# Relay.net
KiCad netlist of a schematic drawn in Altium Designer
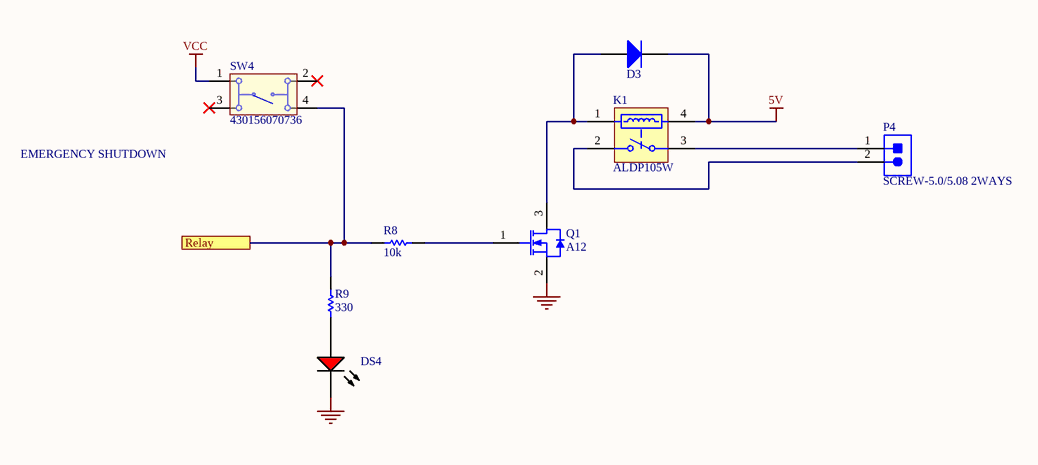
[diagram p0: Relay.SchDoc]

(export (version "E")
  (design (tool "Eeschema 10.0.6"))
  (components
    (comp (ref "D3")
      (value "MMSD4148T3G")
      (footprint "ONSC-SOD123-2-425G-04_V")
      (description "Switching Diode, 100 V, 200 mA, -55 to 150 degC, 2-Pin SOD123 (425), RoHS, Tape and Reel")
      (fields (field (name "MANUFACTURER") "ON Semiconductor"))
      (libsource (lib "Altium Content Vault") (part "ONSC-MMSD4148-SOD123-2"))
    )
    (comp (ref "DS4")
      (value "TLMS1100-GS08")
      (footprint "VISH-TLMX1100_V")
      (description "LED, RED, 2.1 V, -40 to 100 degC, 2-Pin SMD (0603), RoHS, Tape and Reel")
      (fields (field (name "TOLERANCE") "5%"))
      (libsource (lib "Altium Content Vault") (part "LED-RED-AK-2"))
    )
    (comp (ref "K1")
      (value "ALDP105W")
      (footprint "PNSC-LD-P-4-2050x720x1530_V")
      (fields (field (name "MANUFACTURER") "Panasonic"))
      (libsource (lib "Altium Content Vault") (part "PNSC-ALDP105W-LD-P-4-2050x720x1530-4"))
    )
    (comp (ref "P4")
      (value "SCREW-5.0/5.08 2WAYS")
      (footprint "SCREW-5.0-2WAYS_V")
      (description "Socket, Screw Terminal Block, 2 Way, 5.0 mm Pitch, 90 Degree Angle, Through-Hole")
      (fields (field (name "MANUFACTURER") "No Vendor"))
      (libsource (lib "Altium Content Vault") (part "SCREW-2WAYS"))
    )
    (comp (ref "Q1")
      (value "A12")
      (footprint "INTR-SOT-23-3_V")
      (fields (field (name "MANUFACTURER") "International Rectifier"))
      (libsource (lib "Altium Content Vault") (part "NEMOS-GSD-3"))
    )
    (comp (ref "R8")
      (value "10k")
      (footprint "RESC0805(2012)_L")
      (description "10K2 0.125W 1% 0805 (2012 Metric)  SMD")
      (fields (field (name "TOLERANCE") "1 %") (field (name "POWER") "0.125 W"))
      (libsource (lib "Altium Content Vault") (part "RES"))
    )
    (comp (ref "R9")
      (value "330")
      (footprint "RESC0805(2012)_L")
      (description "10K2 0.125W 1% 0805 (2012 Metric)  SMD")
      (fields (field (name "TOLERANCE") "1 %") (field (name "POWER") "0.125 W"))
      (libsource (lib "Altium Content Vault") (part "RES"))
    )
    (comp (ref "SW4")
      (value "430156070736")
      (footprint "430156070736")
      (description "WS-TATV THT Tact Switch 6X6 mm")
      (fields (field (name "MANUFACTURER") "Wuerth Elektronik"))
      (libsource (lib "Altium Content Vault") (part "WE-TACT-SW-4"))
    )
  )
  (nets
    (net (code "1") (name "/Relay") (class "Default")
      (node (ref "R8") (pin "2") (pinfunction "2_2") (pintype "passive"))
      (node (ref "R9") (pin "1") (pinfunction "1_1") (pintype "passive"))
      (node (ref "SW4") (pin "4") (pinfunction "4_4") (pintype "passive"))
    )
    (net (code "2") (name "5V") (class "Default")
      (node (ref "D3") (pin "1") (pinfunction "CATHODE_1") (pintype "passive"))
      (node (ref "K1") (pin "4") (pinfunction "4_4") (pintype "passive"))
    )
    (net (code "3") (name "GND") (class "Default")
      (node (ref "DS4") (pin "2") (pinfunction "K_2") (pintype "passive"))
      (node (ref "Q1") (pin "2") (pinfunction "S_2") (pintype "passive"))
    )
    (net (code "4") (name "Net-(D3-ANODE)") (class "Default")
      (node (ref "D3") (pin "2") (pinfunction "ANODE_2") (pintype "passive"))
      (node (ref "K1") (pin "1") (pinfunction "1_1") (pintype "passive"))
      (node (ref "Q1") (pin "3") (pinfunction "D_3") (pintype "passive"))
    )
    (net (code "5") (name "Net-(DS4-A)") (class "Default")
      (node (ref "DS4") (pin "1") (pinfunction "A_1") (pintype "passive"))
      (node (ref "R9") (pin "2") (pinfunction "2_2") (pintype "passive"))
    )
    (net (code "6") (name "Net-(K1-COM)") (class "Default")
      (node (ref "K1") (pin "3") (pinfunction "COM_3") (pintype "passive"))
      (node (ref "P4") (pin "1") (pinfunction "1_1") (pintype "passive"))
    )
    (net (code "7") (name "Net-(K1-NO)") (class "Default")
      (node (ref "K1") (pin "2") (pinfunction "NO_2") (pintype "passive"))
      (node (ref "P4") (pin "2") (pinfunction "2_2") (pintype "passive"))
    )
    (net (code "8") (name "Net-(Q1-G)") (class "Default")
      (node (ref "Q1") (pin "1") (pinfunction "G_1") (pintype "passive"))
      (node (ref "R8") (pin "1") (pinfunction "1_1") (pintype "passive"))
    )
    (net (code "9") (name "VCC") (class "Default")
      (node (ref "SW4") (pin "1") (pinfunction "1_1") (pintype "passive"))
    )
    (net (code "10") (name "unconnected-(SW4-Pad2)") (class "Default")
      (node (ref "SW4") (pin "2") (pinfunction "2_2") (pintype "passive+no_connect"))
    )
    (net (code "11") (name "unconnected-(SW4-Pad3)") (class "Default")
      (node (ref "SW4") (pin "3") (pinfunction "3_3") (pintype "passive+no_connect"))
    )
  )
)
